# TinkerAccess.net
KiCad netlist of a schematic drawn in EAGLE
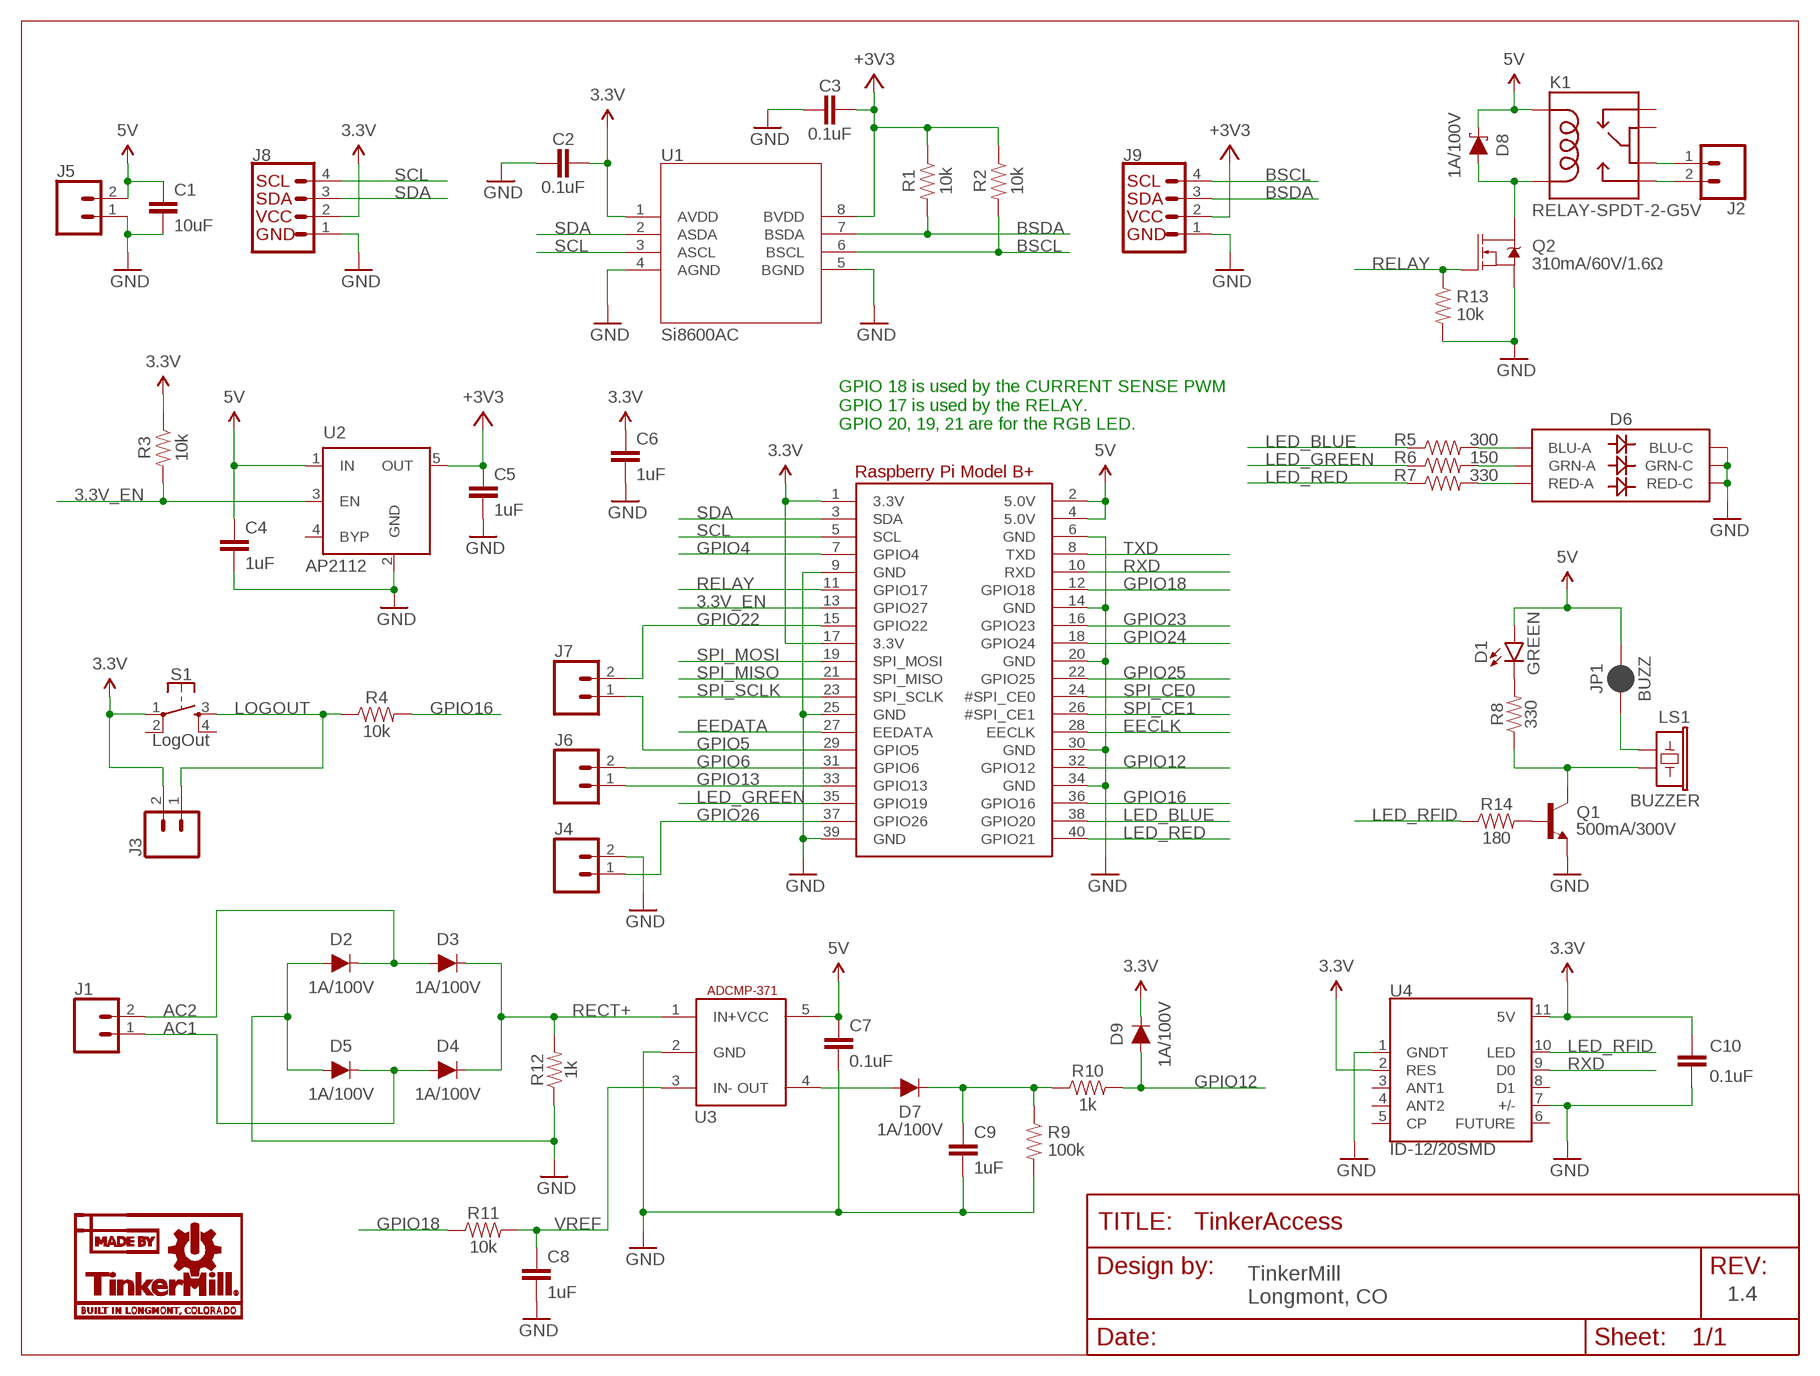
[diagram p0: schematic, sheet 1]

(export (version "E")
  (design (tool "Eeschema 10.0.6"))
  (components
    (comp (ref "C1")
      (value "10uF")
      (footprint "eagle-import:1206")
      (libsource (lib "eagle-import") (part "10UF-1206-6.3V-20%"))
    )
    (comp (ref "C2")
      (value "0.1uF")
      (footprint "eagle-import:0603")
      (libsource (lib "eagle-import") (part "0.1UF-0603-25V-(+80/-20%)"))
    )
    (comp (ref "C3")
      (value "0.1uF")
      (footprint "eagle-import:0603")
      (libsource (lib "eagle-import") (part "0.1UF-0603-25V-(+80/-20%)"))
    )
    (comp (ref "C4")
      (value "1uF")
      (footprint "eagle-import:0603")
      (libsource (lib "eagle-import") (part "10UF-0603-6.3V-20%"))
    )
    (comp (ref "C5")
      (value "1uF")
      (footprint "eagle-import:0603")
      (libsource (lib "eagle-import") (part "10UF-0603-6.3V-20%"))
    )
    (comp (ref "C6")
      (value "1uF")
      (footprint "eagle-import:0603")
      (libsource (lib "eagle-import") (part "10UF-0603-6.3V-20%"))
    )
    (comp (ref "C7")
      (value "0.1uF")
      (footprint "eagle-import:0603")
      (libsource (lib "eagle-import") (part "10UF-0603-6.3V-20%"))
    )
    (comp (ref "C8")
      (value "1uF")
      (footprint "eagle-import:0603")
      (libsource (lib "eagle-import") (part "10UF-0603-6.3V-20%"))
    )
    (comp (ref "C9")
      (value "1uF")
      (footprint "eagle-import:0603")
      (libsource (lib "eagle-import") (part "10UF-0603-6.3V-20%"))
    )
    (comp (ref "C10")
      (value "0.1uF")
      (footprint "eagle-import:0603")
      (libsource (lib "eagle-import") (part "0.1UF-0603-25V-(+80/-20%)"))
    )
    (comp (ref "D1")
      (value "GREEN")
      (footprint "eagle-import:LED-1206")
      (libsource (lib "eagle-import") (part "LED-GREEN1206"))
    )
    (comp (ref "D2")
      (value "1A/100V")
      (footprint "eagle-import:SOD-323")
      (libsource (lib "eagle-import") (part "DIODE-BAS16J"))
    )
    (comp (ref "D3")
      (value "1A/100V")
      (footprint "eagle-import:SOD-323")
      (libsource (lib "eagle-import") (part "DIODE-BAS16J"))
    )
    (comp (ref "D4")
      (value "1A/100V")
      (footprint "eagle-import:SOD-323")
      (libsource (lib "eagle-import") (part "DIODE-BAS16J"))
    )
    (comp (ref "D5")
      (value "1A/100V")
      (footprint "eagle-import:SOD-323")
      (libsource (lib "eagle-import") (part "DIODE-BAS16J"))
    )
    (comp (ref "D6")
      (value "LED-RGBNO_IC")
      (footprint "eagle-import:LED-TRICOLOR-5050")
      (libsource (lib "eagle-import") (part "LED-RGBNO_IC"))
    )
    (comp (ref "D7")
      (value "1A/100V")
      (footprint "eagle-import:SOD-323")
      (libsource (lib "eagle-import") (part "DIODE-BAS16J"))
    )
    (comp (ref "D8")
      (value "1A/100V")
      (footprint "eagle-import:SOD-323")
      (libsource (lib "eagle-import") (part "DIODE-SCHOTTKY-BAT20J"))
    )
    (comp (ref "D9")
      (value "1A/100V")
      (footprint "eagle-import:SOD-323")
      (libsource (lib "eagle-import") (part "DIODE-BAS16J"))
    )
    (comp (ref "J1")
      (value "CONN_025MM")
      (footprint "eagle-import:SCREWTERMINAL-5MM-2")
      (libsource (lib "eagle-import") (part "CONN_025MM"))
    )
    (comp (ref "J2")
      (value "CONN_025MM")
      (footprint "eagle-import:SCREWTERMINAL-5MM-2")
      (libsource (lib "eagle-import") (part "CONN_025MM"))
    )
    (comp (ref "J3")
      (value "CONN_025MM")
      (footprint "eagle-import:SCREWTERMINAL-5MM-2")
      (libsource (lib "eagle-import") (part "CONN_025MM"))
    )
    (comp (ref "J4")
      (value "CONN_025MM")
      (footprint "eagle-import:SCREWTERMINAL-5MM-2")
      (libsource (lib "eagle-import") (part "CONN_025MM"))
    )
    (comp (ref "J5")
      (value "CONN_025MM")
      (footprint "eagle-import:SCREWTERMINAL-5MM-2")
      (libsource (lib "eagle-import") (part "CONN_025MM"))
    )
    (comp (ref "J6")
      (value "CONN_025MM")
      (footprint "eagle-import:SCREWTERMINAL-5MM-2")
      (libsource (lib "eagle-import") (part "CONN_025MM"))
    )
    (comp (ref "J7")
      (value "CONN_025MM")
      (footprint "eagle-import:SCREWTERMINAL-5MM-2")
      (libsource (lib "eagle-import") (part "CONN_025MM"))
    )
    (comp (ref "J8")
      (value "QWIIC_CONNECTORJS-1MM")
      (footprint "eagle-import:1X04_1MM_RA")
      (libsource (lib "eagle-import") (part "QWIIC_CONNECTORJS-1MM"))
    )
    (comp (ref "J9")
      (value "QWIIC_CONNECTORJS-1MM")
      (footprint "eagle-import:1X04_1MM_RA")
      (libsource (lib "eagle-import") (part "QWIIC_CONNECTORJS-1MM"))
    )
    (comp (ref "JP1")
      (value "BUZZ")
      (footprint "eagle-import:SMT-JUMPER_2_NC_PASTE_NO-SILK")
      (libsource (lib "eagle-import") (part "JUMPER-SMT_2_NC_PASTE_NO-SILK"))
    )
    (comp (ref "K1")
      (value "RELAY-SPDT-2-G5V")
      (footprint "eagle-import:RELAY-G5V")
      (libsource (lib "eagle-import") (part "RELAY-SPDT-2-G5V"))
    )
    (comp (ref "LOGO1")
      (value "MADE_BY_TINKERMILL")
      (footprint "eagle-import:MADE_BY_TINKERMILL")
      (libsource (lib "eagle-import") (part "MADE_BY_TINKERMILL"))
    )
    (comp (ref "LS1")
      (value "BUZZER")
      (footprint "eagle-import:BUZZER-CCV")
      (libsource (lib "eagle-import") (part "BUZZER-SMD"))
    )
    (comp (ref "Q1")
      (value "500mA/300V")
      (footprint "eagle-import:SOT23-3")
      (libsource (lib "eagle-import") (part "TRANS_NPN-MMBTA42"))
    )
    (comp (ref "Q2")
      (value "310mA/60V/1.6Ω")
      (footprint "eagle-import:SOT323")
      (libsource (lib "eagle-import") (part "MOSFET-NCH-2N7002PW"))
    )
    (comp (ref "R1")
      (value "10k")
      (footprint "eagle-import:0603")
      (libsource (lib "eagle-import") (part "10KOHM-0603-1/10W-1%"))
    )
    (comp (ref "R2")
      (value "10k")
      (footprint "eagle-import:0603")
      (libsource (lib "eagle-import") (part "10KOHM-0603-1/10W-1%"))
    )
    (comp (ref "R3")
      (value "10k")
      (footprint "eagle-import:0603")
      (libsource (lib "eagle-import") (part "10KOHM-0603-1/10W-1%"))
    )
    (comp (ref "R4")
      (value "10k")
      (footprint "eagle-import:0603")
      (libsource (lib "eagle-import") (part "10KOHM-0603-1/10W-1%"))
    )
    (comp (ref "R5")
      (value "300")
      (footprint "eagle-import:0603")
      (libsource (lib "eagle-import") (part "300OHM-0603-1/10W-1%"))
    )
    (comp (ref "R6")
      (value "150")
      (footprint "eagle-import:0603")
      (libsource (lib "eagle-import") (part "150OHM-0603-1/10W-1%"))
    )
    (comp (ref "R7")
      (value "330")
      (footprint "eagle-import:0603")
      (libsource (lib "eagle-import") (part "330OHM-0603-1/10W-1%"))
    )
    (comp (ref "R8")
      (value "330")
      (footprint "eagle-import:0603")
      (libsource (lib "eagle-import") (part "10MOHM-0603-1/10W-5%"))
    )
    (comp (ref "R9")
      (value "100k")
      (footprint "eagle-import:0603")
      (libsource (lib "eagle-import") (part "1KOHM-0603-1/10W-1%"))
    )
    (comp (ref "R10")
      (value "1k")
      (footprint "eagle-import:0603")
      (libsource (lib "eagle-import") (part "1KOHM-0603-1/10W-1%"))
    )
    (comp (ref "R11")
      (value "10k")
      (footprint "eagle-import:0603")
      (libsource (lib "eagle-import") (part "1KOHM-0603-1/10W-1%"))
    )
    (comp (ref "R12")
      (value "1k")
      (footprint "eagle-import:0603")
      (libsource (lib "eagle-import") (part "1KOHM-0603-1/10W-1%"))
    )
    (comp (ref "R13")
      (value "10k")
      (footprint "eagle-import:0603")
      (libsource (lib "eagle-import") (part "1KOHM-0603-1/10W-1%"))
    )
    (comp (ref "R14")
      (value "180")
      (footprint "eagle-import:0603")
      (libsource (lib "eagle-import") (part "10MOHM-0603-1/10W-5%"))
    )
    (comp (ref "RPI1")
      (value "RASPBERRYPI_BPLUS_HATNOSLOTS")
      (footprint "eagle-import:PI_HAT_NOSLOTS")
      (libsource (lib "eagle-import") (part "RASPBERRYPI_BPLUS_HATNOSLOTS"))
    )
    (comp (ref "S1")
      (value "LogOut")
      (footprint "eagle-import:TACTILE_SWITCH_SMD_5.2MM")
      (libsource (lib "eagle-import") (part "MOMENTARY-SWITCH-SPST-2-SMD-5.2MM"))
    )
    (comp (ref "U1")
      (value "Si8600AC")
      (footprint "eagle-import:SOIC127P600X175-8")
      (libsource (lib "eagle-import") (part "SI8600SO-8"))
    )
    (comp (ref "U2")
      (value "AP2112")
      (footprint "eagle-import:SOT23-5")
      (libsource (lib "eagle-import") (part "MIC5219XX"))
    )
    (comp (ref "U3")
      (value "ADCMP-371")
      (footprint "eagle-import:SC-70-5")
      (libsource (lib "eagle-import") (part "ADCMP-371"))
    )
    (comp (ref "U4")
      (value "ID-12/20SMD")
      (footprint "eagle-import:ID-12_SMD")
      (libsource (lib "eagle-import") (part "ID-12/20SMD"))
    )
  )
  (nets
    (net (code "1") (name "+3V3") (class "Default")
      (node (ref "C3") (pin "2") (pinfunction "2_2") (pintype "passive"))
      (node (ref "C5") (pin "1") (pinfunction "1_1") (pintype "passive"))
      (node (ref "J9") (pin "2") (pinfunction "VCC_2") (pintype "power_in"))
      (node (ref "R1") (pin "1") (pinfunction "1_1") (pintype "passive"))
      (node (ref "R2") (pin "1") (pinfunction "1_1") (pintype "passive"))
      (node (ref "U1") (pin "8") (pinfunction "BVDD_8") (pintype "bidirectional"))
      (node (ref "U2") (pin "5") (pinfunction "OUT_5") (pintype "output"))
    )
    (net (code "2") (name "/3.3V_EN") (class "Default")
      (node (ref "R3") (pin "2") (pinfunction "2_2") (pintype "passive"))
      (node (ref "RPI1") (pin "13") (pinfunction "GPIO27_13") (pintype "bidirectional"))
      (node (ref "U2") (pin "3") (pinfunction "EN_3") (pintype "input"))
    )
    (net (code "3") (name "/AC1") (class "Default")
      (node (ref "D4") (pin "A") (pinfunction "A_A") (pintype "passive"))
      (node (ref "D5") (pin "C") (pinfunction "C_C") (pintype "passive"))
      (node (ref "J1") (pin "1") (pinfunction "1_1") (pintype "passive"))
    )
    (net (code "4") (name "/AC2") (class "Default")
      (node (ref "D2") (pin "C") (pinfunction "C_C") (pintype "passive"))
      (node (ref "D3") (pin "A") (pinfunction "A_A") (pintype "passive"))
      (node (ref "J1") (pin "2") (pinfunction "2_2") (pintype "passive"))
    )
    (net (code "5") (name "/BSCL") (class "Default")
      (node (ref "J9") (pin "4") (pinfunction "SCL_4") (pintype "passive"))
      (node (ref "R2") (pin "2") (pinfunction "2_2") (pintype "passive"))
      (node (ref "U1") (pin "6") (pinfunction "BSCL_6") (pintype "bidirectional"))
    )
    (net (code "6") (name "/BSDA") (class "Default")
      (node (ref "J9") (pin "3") (pinfunction "SDA_3") (pintype "passive"))
      (node (ref "R1") (pin "2") (pinfunction "2_2") (pintype "passive"))
      (node (ref "U1") (pin "7") (pinfunction "BSDA_7") (pintype "bidirectional"))
    )
    (net (code "7") (name "/EECLK") (class "Default")
      (node (ref "RPI1") (pin "28") (pinfunction "EECLK_28") (pintype "power_in"))
    )
    (net (code "8") (name "/EEDATA") (class "Default")
      (node (ref "RPI1") (pin "27") (pinfunction "EEDATA_27") (pintype "bidirectional"))
    )
    (net (code "9") (name "/GPIO4") (class "Default")
      (node (ref "RPI1") (pin "7") (pinfunction "GPIO4_7") (pintype "bidirectional"))
    )
    (net (code "10") (name "/GPIO5") (class "Default")
      (node (ref "J7") (pin "1") (pinfunction "1_1") (pintype "passive"))
      (node (ref "RPI1") (pin "29") (pinfunction "GPIO5_29") (pintype "bidirectional"))
    )
    (net (code "11") (name "/GPIO6") (class "Default")
      (node (ref "J6") (pin "2") (pinfunction "2_2") (pintype "passive"))
      (node (ref "RPI1") (pin "31") (pinfunction "GPIO6_31") (pintype "power_in"))
    )
    (net (code "12") (name "/GPIO12") (class "Default")
      (node (ref "D9") (pin "A") (pinfunction "A_A") (pintype "passive"))
      (node (ref "R10") (pin "2") (pinfunction "2_2") (pintype "passive"))
      (node (ref "RPI1") (pin "32") (pinfunction "GPIO12_32") (pintype "bidirectional"))
    )
    (net (code "13") (name "/GPIO13") (class "Default")
      (node (ref "J6") (pin "1") (pinfunction "1_1") (pintype "passive"))
      (node (ref "RPI1") (pin "33") (pinfunction "GPIO13_33") (pintype "bidirectional"))
    )
    (net (code "14") (name "/GPIO16") (class "Default")
      (node (ref "R4") (pin "2") (pinfunction "2_2") (pintype "passive"))
      (node (ref "RPI1") (pin "36") (pinfunction "GPIO16_36") (pintype "power_in"))
    )
    (net (code "15") (name "/GPIO18") (class "Default")
      (node (ref "R11") (pin "1") (pinfunction "1_1") (pintype "passive"))
      (node (ref "RPI1") (pin "12") (pinfunction "GPIO18_12") (pintype "bidirectional"))
    )
    (net (code "16") (name "/GPIO22") (class "Default")
      (node (ref "J7") (pin "2") (pinfunction "2_2") (pintype "passive"))
      (node (ref "RPI1") (pin "15") (pinfunction "GPIO22_15") (pintype "bidirectional"))
    )
    (net (code "17") (name "/GPIO23") (class "Default")
      (node (ref "RPI1") (pin "16") (pinfunction "GPIO23_16") (pintype "bidirectional"))
    )
    (net (code "18") (name "/GPIO24") (class "Default")
      (node (ref "RPI1") (pin "18") (pinfunction "GPIO24_18") (pintype "bidirectional"))
    )
    (net (code "19") (name "/GPIO25") (class "Default")
      (node (ref "RPI1") (pin "22") (pinfunction "GPIO25_22") (pintype "bidirectional"))
    )
    (net (code "20") (name "/GPIO26") (class "Default")
      (node (ref "J4") (pin "1") (pinfunction "1_1") (pintype "passive"))
      (node (ref "RPI1") (pin "37") (pinfunction "GPIO26_37") (pintype "bidirectional"))
    )
    (net (code "21") (name "/LED_BLUE") (class "Default")
      (node (ref "R5") (pin "1") (pinfunction "1_1") (pintype "passive"))
      (node (ref "RPI1") (pin "38") (pinfunction "GPIO20_38") (pintype "bidirectional"))
    )
    (net (code "22") (name "/LED_GREEN") (class "Default")
      (node (ref "R6") (pin "1") (pinfunction "1_1") (pintype "passive"))
      (node (ref "RPI1") (pin "35") (pinfunction "GPIO19_35") (pintype "bidirectional"))
    )
    (net (code "23") (name "/LED_RED") (class "Default")
      (node (ref "R7") (pin "1") (pinfunction "1_1") (pintype "passive"))
      (node (ref "RPI1") (pin "40") (pinfunction "GPIO21_40") (pintype "bidirectional"))
    )
    (net (code "24") (name "/LED_RFID") (class "Default")
      (node (ref "R14") (pin "1") (pinfunction "1_1") (pintype "passive"))
      (node (ref "U4") (pin "10") (pinfunction "LED_10") (pintype "bidirectional"))
    )
    (net (code "25") (name "/LOGOUT") (class "Default")
      (node (ref "J3") (pin "1") (pinfunction "1_1") (pintype "passive"))
      (node (ref "R4") (pin "1") (pinfunction "1_1") (pintype "passive"))
      (node (ref "S1") (pin "3") (pinfunction "3_3") (pintype "passive"))
    )
    (net (code "26") (name "/RECT+") (class "Default")
      (node (ref "D3") (pin "C") (pinfunction "C_C") (pintype "passive"))
      (node (ref "D4") (pin "C") (pinfunction "C_C") (pintype "passive"))
      (node (ref "R12") (pin "2") (pinfunction "2_2") (pintype "passive"))
      (node (ref "U3") (pin "1") (pinfunction "IN+_1") (pintype "bidirectional"))
    )
    (net (code "27") (name "/RELAY") (class "Default")
      (node (ref "Q2") (pin "1") (pinfunction "G_1") (pintype "bidirectional"))
      (node (ref "R13") (pin "1") (pinfunction "1_1") (pintype "passive"))
      (node (ref "RPI1") (pin "11") (pinfunction "GPIO17_11") (pintype "bidirectional"))
    )
    (net (code "28") (name "/RXD") (class "Default")
      (node (ref "RPI1") (pin "10") (pinfunction "RXD_10") (pintype "bidirectional"))
      (node (ref "U4") (pin "9") (pinfunction "D0_9") (pintype "bidirectional"))
    )
    (net (code "29") (name "/SCL") (class "Default")
      (node (ref "J8") (pin "4") (pinfunction "SCL_4") (pintype "passive"))
      (node (ref "RPI1") (pin "5") (pinfunction "SCL_5") (pintype "bidirectional"))
      (node (ref "U1") (pin "3") (pinfunction "ASCL_3") (pintype "bidirectional"))
    )
    (net (code "30") (name "/SDA") (class "Default")
      (node (ref "J8") (pin "3") (pinfunction "SDA_3") (pintype "passive"))
      (node (ref "RPI1") (pin "3") (pinfunction "SDA_3") (pintype "bidirectional"))
      (node (ref "U1") (pin "2") (pinfunction "ASDA_2") (pintype "bidirectional"))
    )
    (net (code "31") (name "/SPI_CE0") (class "Default")
      (node (ref "RPI1") (pin "24") (pinfunction "#SPI_CE0_24") (pintype "bidirectional"))
    )
    (net (code "32") (name "/SPI_CE1") (class "Default")
      (node (ref "RPI1") (pin "26") (pinfunction "#SPI_CE1_26") (pintype "bidirectional"))
    )
    (net (code "33") (name "/SPI_MISO") (class "Default")
      (node (ref "RPI1") (pin "21") (pinfunction "SPI_MISO_21") (pintype "bidirectional"))
    )
    (net (code "34") (name "/SPI_MOSI") (class "Default")
      (node (ref "RPI1") (pin "19") (pinfunction "SPI_MOSI_19") (pintype "bidirectional"))
    )
    (net (code "35") (name "/SPI_SCLK") (class "Default")
      (node (ref "RPI1") (pin "23") (pinfunction "SPI_SCLK_23") (pintype "bidirectional"))
    )
    (net (code "36") (name "/TXD") (class "Default")
      (node (ref "RPI1") (pin "8") (pinfunction "TXD_8") (pintype "output"))
    )
    (net (code "37") (name "/VREF") (class "Default")
      (node (ref "C8") (pin "1") (pinfunction "1_1") (pintype "passive"))
      (node (ref "R11") (pin "2") (pinfunction "2_2") (pintype "passive"))
      (node (ref "U3") (pin "3") (pinfunction "IN-_3") (pintype "bidirectional"))
    )
    (net (code "38") (name "3.3V") (class "Default")
      (node (ref "C10") (pin "2") (pinfunction "2_2") (pintype "passive"))
      (node (ref "C2") (pin "2") (pinfunction "2_2") (pintype "passive"))
      (node (ref "C6") (pin "1") (pinfunction "1_1") (pintype "passive"))
      (node (ref "D9") (pin "C") (pinfunction "C_C") (pintype "passive"))
      (node (ref "J3") (pin "2") (pinfunction "2_2") (pintype "passive"))
      (node (ref "J8") (pin "2") (pinfunction "VCC_2") (pintype "power_in"))
      (node (ref "R3") (pin "1") (pinfunction "1_1") (pintype "passive"))
      (node (ref "RPI1") (pin "1") (pinfunction "3.3V_1") (pintype "power_in"))
      (node (ref "RPI1") (pin "17") (pinfunction "3.3V_17") (pintype "power_in"))
      (node (ref "S1") (pin "1") (pinfunction "1_1") (pintype "passive"))
      (node (ref "U1") (pin "1") (pinfunction "AVDD_1") (pintype "bidirectional"))
      (node (ref "U4") (pin "11") (pinfunction "5V_11") (pintype "bidirectional"))
      (node (ref "U4") (pin "2") (pinfunction "RES_2") (pintype "bidirectional"))
    )
    (net (code "39") (name "5V") (class "Default")
      (node (ref "C1") (pin "1") (pinfunction "1_1") (pintype "passive"))
      (node (ref "C4") (pin "1") (pinfunction "1_1") (pintype "passive"))
      (node (ref "C7") (pin "1") (pinfunction "1_1") (pintype "passive"))
      (node (ref "D1") (pin "A") (pinfunction "A_A") (pintype "passive"))
      (node (ref "D8") (pin "C") (pinfunction "C_C") (pintype "passive"))
      (node (ref "J5") (pin "2") (pinfunction "2_2") (pintype "passive"))
      (node (ref "JP1") (pin "2") (pinfunction "2_2") (pintype "passive"))
      (node (ref "K1") (pin "2") (pinfunction "2_2") (pintype "bidirectional"))
      (node (ref "RPI1") (pin "2") (pinfunction "5.0V_2") (pintype "power_in"))
      (node (ref "RPI1") (pin "4") (pinfunction "5.0V_4") (pintype "power_in"))
      (node (ref "U2") (pin "1") (pinfunction "IN_1") (pintype "input"))
      (node (ref "U3") (pin "5") (pinfunction "VCC_5") (pintype "bidirectional"))
    )
    (net (code "40") (name "GND") (class "Default")
      (node (ref "C1") (pin "2") (pinfunction "2_2") (pintype "passive"))
      (node (ref "C10") (pin "1") (pinfunction "1_1") (pintype "passive"))
      (node (ref "C2") (pin "1") (pinfunction "1_1") (pintype "passive"))
      (node (ref "C3") (pin "1") (pinfunction "1_1") (pintype "passive"))
      (node (ref "C4") (pin "2") (pinfunction "2_2") (pintype "passive"))
      (node (ref "C5") (pin "2") (pinfunction "2_2") (pintype "passive"))
      (node (ref "C6") (pin "2") (pinfunction "2_2") (pintype "passive"))
      (node (ref "C7") (pin "2") (pinfunction "2_2") (pintype "passive"))
      (node (ref "C8") (pin "2") (pinfunction "2_2") (pintype "passive"))
      (node (ref "C9") (pin "2") (pinfunction "2_2") (pintype "passive"))
      (node (ref "D2") (pin "A") (pinfunction "A_A") (pintype "passive"))
      (node (ref "D5") (pin "A") (pinfunction "A_A") (pintype "passive"))
      (node (ref "D6") (pin "4") (pinfunction "BLU-C_4") (pintype "bidirectional"))
      (node (ref "D6") (pin "5") (pinfunction "RED-C_5") (pintype "bidirectional"))
      (node (ref "D6") (pin "6") (pinfunction "GRN-C_6") (pintype "bidirectional"))
      (node (ref "J4") (pin "2") (pinfunction "2_2") (pintype "passive"))
      (node (ref "J5") (pin "1") (pinfunction "1_1") (pintype "passive"))
      (node (ref "J8") (pin "1") (pinfunction "GND_1") (pintype "power_in"))
      (node (ref "J9") (pin "1") (pinfunction "GND_1") (pintype "power_in"))
      (node (ref "Q1") (pin "2") (pinfunction "E_2") (pintype "passive"))
      (node (ref "Q2") (pin "2") (pinfunction "S_2") (pintype "bidirectional"))
      (node (ref "R12") (pin "1") (pinfunction "1_1") (pintype "passive"))
      (node (ref "R13") (pin "2") (pinfunction "2_2") (pintype "passive"))
      (node (ref "R9") (pin "2") (pinfunction "2_2") (pintype "passive"))
      (node (ref "RPI1") (pin "14") (pinfunction "GND_14") (pintype "power_in"))
      (node (ref "RPI1") (pin "20") (pinfunction "GND_20") (pintype "power_in"))
      (node (ref "RPI1") (pin "25") (pinfunction "GND_25") (pintype "power_in"))
      (node (ref "RPI1") (pin "30") (pinfunction "GND_30") (pintype "bidirectional"))
      (node (ref "RPI1") (pin "34") (pinfunction "GND_34") (pintype "bidirectional"))
      (node (ref "RPI1") (pin "39") (pinfunction "GND_39") (pintype "power_in"))
      (node (ref "RPI1") (pin "6") (pinfunction "GND_6") (pintype "power_in"))
      (node (ref "RPI1") (pin "9") (pinfunction "GND_9") (pintype "power_in"))
      (node (ref "U1") (pin "4") (pinfunction "AGND_4") (pintype "bidirectional"))
      (node (ref "U1") (pin "5") (pinfunction "BGND_5") (pintype "bidirectional"))
      (node (ref "U2") (pin "2") (pinfunction "GND_2") (pintype "power_in"))
      (node (ref "U3") (pin "2") (pinfunction "GND_2") (pintype "bidirectional"))
      (node (ref "U4") (pin "1") (pinfunction "GNDT_1") (pintype "bidirectional"))
      (node (ref "U4") (pin "7") (pinfunction "+/-_7") (pintype "bidirectional"))
    )
    (net (code "41") (name "Net-(C9-Pad1)") (class "Default")
      (node (ref "C9") (pin "1") (pinfunction "1_1") (pintype "passive"))
      (node (ref "D7") (pin "C") (pinfunction "C_C") (pintype "passive"))
      (node (ref "R10") (pin "1") (pinfunction "1_1") (pintype "passive"))
      (node (ref "R9") (pin "1") (pinfunction "1_1") (pintype "passive"))
    )
    (net (code "42") (name "Net-(D1-PadC)") (class "Default")
      (node (ref "D1") (pin "C") (pinfunction "C_C") (pintype "passive"))
      (node (ref "R8") (pin "2") (pinfunction "2_2") (pintype "passive"))
    )
    (net (code "43") (name "Net-(D6-BLU-A)") (class "Default")
      (node (ref "D6") (pin "3") (pinfunction "BLU-A_3") (pintype "bidirectional"))
      (node (ref "R5") (pin "2") (pinfunction "2_2") (pintype "passive"))
    )
    (net (code "44") (name "Net-(D6-GRN-A)") (class "Default")
      (node (ref "D6") (pin "1") (pinfunction "GRN-A_1") (pintype "bidirectional"))
      (node (ref "R6") (pin "2") (pinfunction "2_2") (pintype "passive"))
    )
    (net (code "45") (name "Net-(D6-RED-A)") (class "Default")
      (node (ref "D6") (pin "2") (pinfunction "RED-A_2") (pintype "bidirectional"))
      (node (ref "R7") (pin "2") (pinfunction "2_2") (pintype "passive"))
    )
    (net (code "46") (name "Net-(J2-Pad1)") (class "Default")
      (node (ref "J2") (pin "1") (pinfunction "1_1") (pintype "passive"))
      (node (ref "K1") (pin "6") (pinfunction "6_6") (pintype "bidirectional"))
    )
    (net (code "47") (name "Net-(J2-Pad2)") (class "Default")
      (node (ref "J2") (pin "2") (pinfunction "2_2") (pintype "passive"))
      (node (ref "K1") (pin "10") (pinfunction "10_10") (pintype "bidirectional"))
    )
    (net (code "48") (name "Net-(LS1-1)") (class "Default")
      (node (ref "JP1") (pin "1") (pinfunction "1_1") (pintype "passive"))
      (node (ref "LS1") (pin "+") (pinfunction "1_+") (pintype "passive"))
    )
    (net (code "49") (name "Net-(LS1-2)") (class "Default")
      (node (ref "LS1") (pin "-") (pinfunction "2_-") (pintype "passive"))
      (node (ref "Q1") (pin "3") (pinfunction "C_3") (pintype "passive"))
      (node (ref "R8") (pin "1") (pinfunction "1_1") (pintype "passive"))
    )
    (net (code "50") (name "Net-(Q1-B)") (class "Default")
      (node (ref "Q1") (pin "1") (pinfunction "B_1") (pintype "passive"))
      (node (ref "R14") (pin "2") (pinfunction "2_2") (pintype "passive"))
    )
    (net (code "51") (name "Net-(Q2-D)") (class "Default")
      (node (ref "D8") (pin "A") (pinfunction "A_A") (pintype "passive"))
      (node (ref "K1") (pin "9") (pinfunction "9_9") (pintype "bidirectional"))
      (node (ref "Q2") (pin "3") (pinfunction "D_3") (pintype "bidirectional"))
    )
    (net (code "52") (name "Net-(U3-OUT)") (class "Default")
      (node (ref "D7") (pin "A") (pinfunction "A_A") (pintype "passive"))
      (node (ref "U3") (pin "4") (pinfunction "OUT_4") (pintype "bidirectional"))
    )
    (net (code "53") (name "unconnected-(K1-Pad1)") (class "Default")
      (node (ref "K1") (pin "1") (pinfunction "1_1") (pintype "bidirectional"))
    )
    (net (code "54") (name "unconnected-(K1-Pad5)") (class "Default")
      (node (ref "K1") (pin "5") (pinfunction "5_5") (pintype "bidirectional"))
    )
    (net (code "55") (name "unconnected-(S1-Pad2)") (class "Default")
      (node (ref "S1") (pin "2") (pinfunction "2_2") (pintype "passive"))
    )
    (net (code "56") (name "unconnected-(S1-Pad4)") (class "Default")
      (node (ref "S1") (pin "4") (pinfunction "4_4") (pintype "passive"))
    )
    (net (code "57") (name "unconnected-(U2-BYP-Pad4)") (class "Default")
      (node (ref "U2") (pin "4") (pinfunction "BYP_4") (pintype "passive"))
    )
    (net (code "58") (name "unconnected-(U4-ANT1-Pad3)") (class "Default")
      (node (ref "U4") (pin "3") (pinfunction "ANT1_3") (pintype "bidirectional"))
    )
    (net (code "59") (name "unconnected-(U4-ANT2-Pad4)") (class "Default")
      (node (ref "U4") (pin "4") (pinfunction "ANT2_4") (pintype "bidirectional"))
    )
    (net (code "60") (name "unconnected-(U4-CP-Pad5)") (class "Default")
      (node (ref "U4") (pin "5") (pinfunction "CP_5") (pintype "bidirectional"))
    )
    (net (code "61") (name "unconnected-(U4-D1-Pad8)") (class "Default")
      (node (ref "U4") (pin "8") (pinfunction "D1_8") (pintype "bidirectional"))
    )
    (net (code "62") (name "unconnected-(U4-FUTURE-Pad6)") (class "Default")
      (node (ref "U4") (pin "6") (pinfunction "FUTURE_6") (pintype "bidirectional"))
    )
  )
)
